# Volterra_Doughter_Board_MKS_GEN_L_2_1.net
KiCad netlist of a schematic drawn in EAGLE
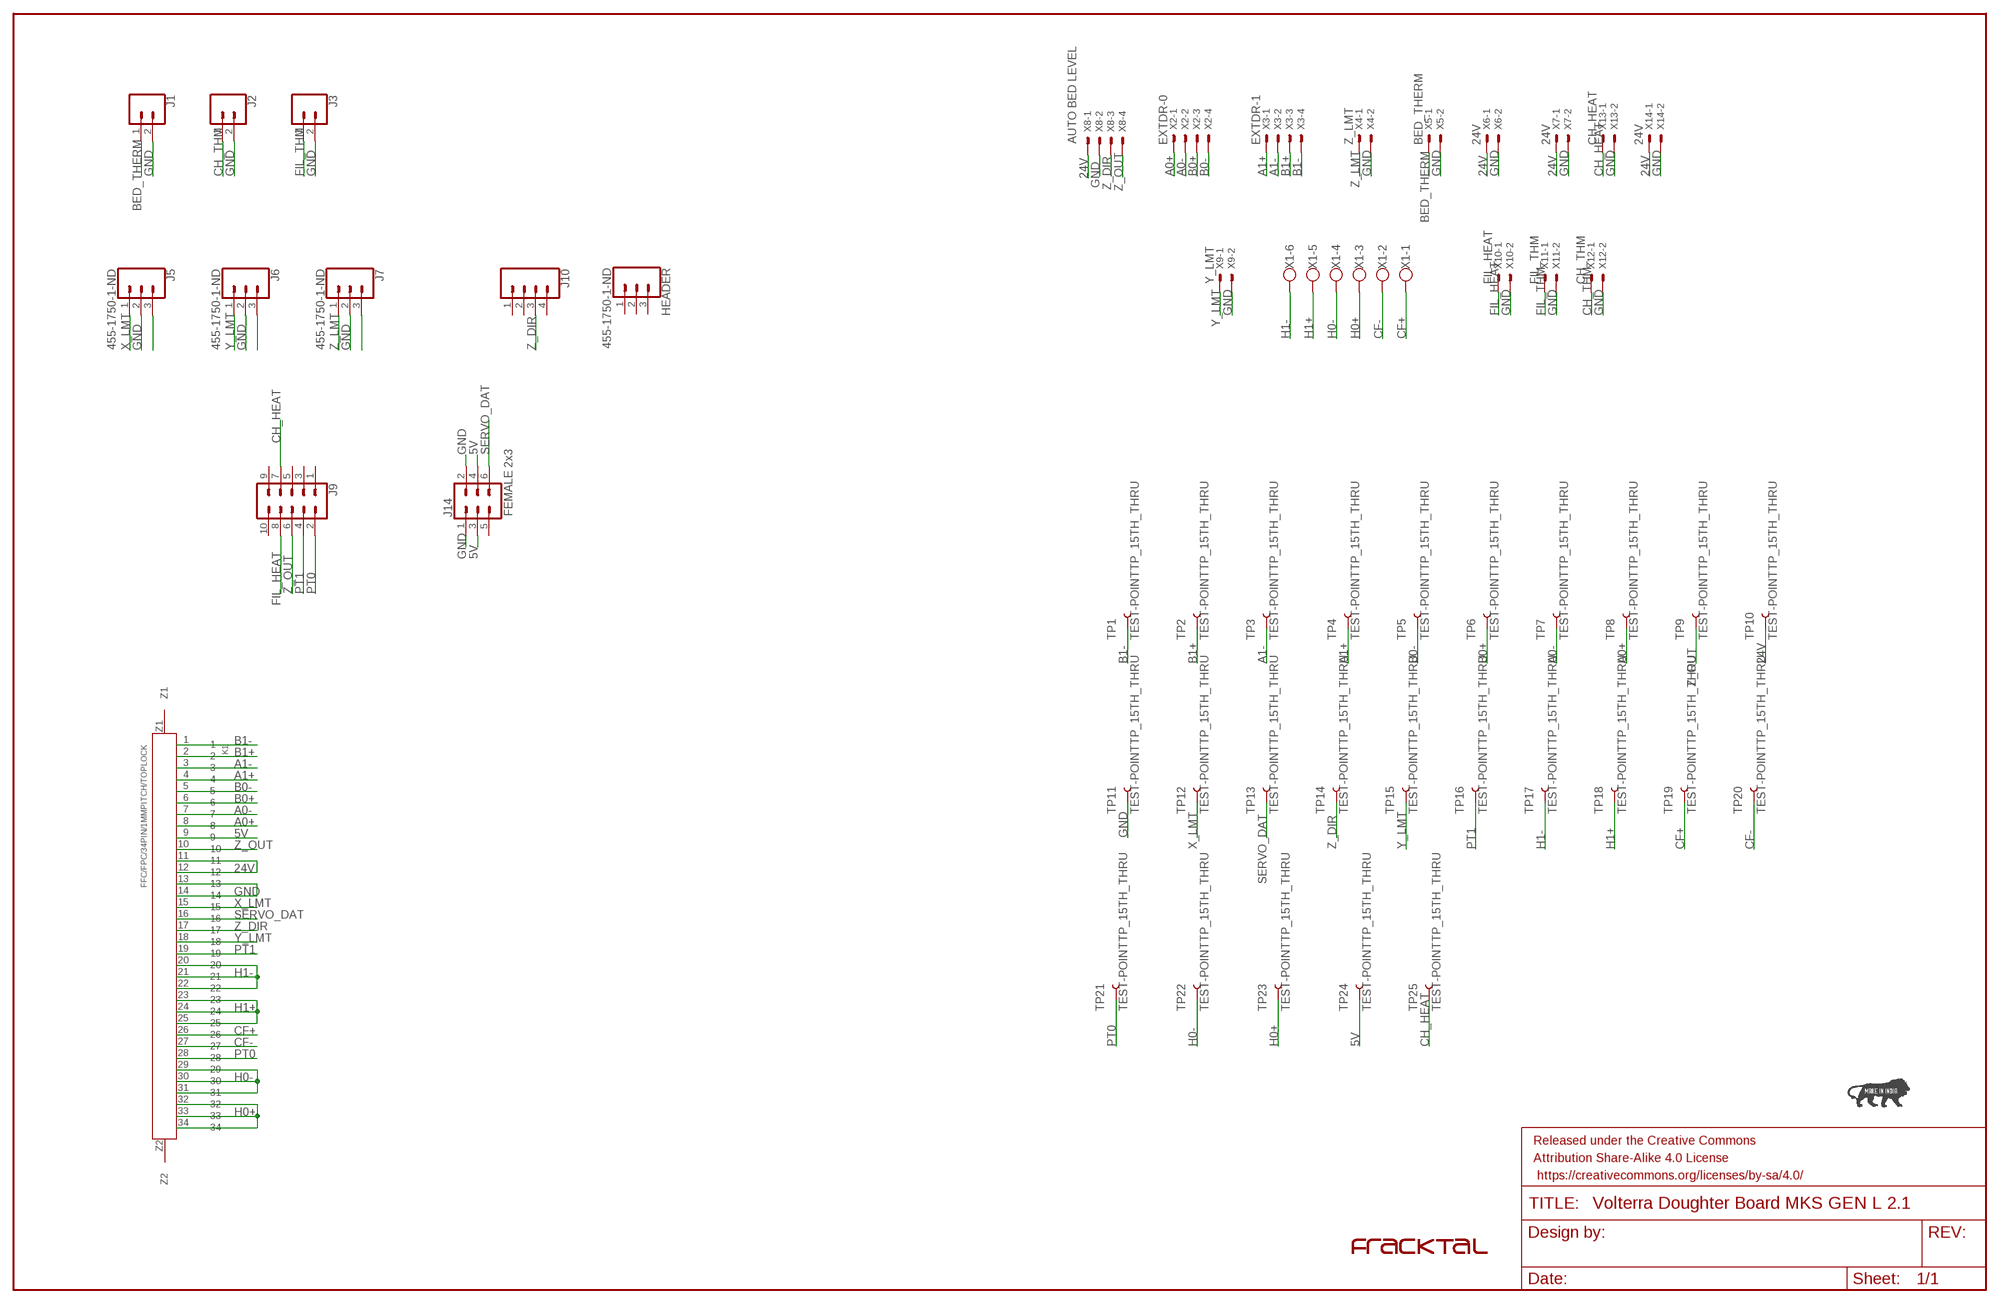
[diagram p0: schematic, sheet 1]

(export (version "E")
  (design (tool "Eeschema 10.0.6"))
  (components
    (comp (ref "FRAME1")
      (value "FRAME-LEDGER")
      (footprint "eagle-import:CREATIVE_COMMONS")
      (libsource (lib "eagle-import") (part "FRAME-LEDGER"))
    )
    (comp (ref "HEADER")
      (value "455-1750-1-ND")
      (footprint "eagle-import:1X03")
      (libsource (lib "eagle-import") (part "CONN_03"))
    )
    (comp (ref "J1")
      (value "CONN_02")
      (footprint "eagle-import:1X02")
      (libsource (lib "eagle-import") (part "CONN_02"))
    )
    (comp (ref "J2")
      (value "CONN_02")
      (footprint "eagle-import:1X02")
      (libsource (lib "eagle-import") (part "CONN_02"))
    )
    (comp (ref "J3")
      (value "CONN_02")
      (footprint "eagle-import:1X02")
      (libsource (lib "eagle-import") (part "CONN_02"))
    )
    (comp (ref "J5")
      (value "455-1750-1-ND")
      (footprint "eagle-import:1X03")
      (libsource (lib "eagle-import") (part "CONN_03"))
    )
    (comp (ref "J6")
      (value "455-1750-1-ND")
      (footprint "eagle-import:1X03")
      (libsource (lib "eagle-import") (part "CONN_03"))
    )
    (comp (ref "J7")
      (value "455-1750-1-ND")
      (footprint "eagle-import:1X03")
      (libsource (lib "eagle-import") (part "CONN_03"))
    )
    (comp (ref "J9")
      (value "CONN_05X2PTH")
      (footprint "eagle-import:2X5")
      (libsource (lib "eagle-import") (part "CONN_05X2PTH"))
    )
    (comp (ref "J10")
      (value "CONN_04")
      (footprint "eagle-import:1X04")
      (libsource (lib "eagle-import") (part "CONN_04"))
    )
    (comp (ref "J14")
      (value "FEMALE 2x3")
      (footprint "eagle-import:2X3")
      (libsource (lib "eagle-import") (part "CONN_03X2FEMALE"))
    )
    (comp (ref "K1")
      (value "FFC/FPC/34PIN/1MMPITCH/TOPLOCK")
      (footprint "eagle-import:34PIN_1MMPITCH_FFC_FPC")
      (libsource (lib "eagle-import") (part "FFC/FPC/34PIN/1MMPITCH/TOPLOCK"))
    )
    (comp (ref "TP1")
      (value "TEST-POINTTP_15TH_THRU")
      (footprint "eagle-import:TP_15TH")
      (libsource (lib "eagle-import") (part "TEST-POINTTP_15TH_THRU"))
    )
    (comp (ref "TP2")
      (value "TEST-POINTTP_15TH_THRU")
      (footprint "eagle-import:TP_15TH")
      (libsource (lib "eagle-import") (part "TEST-POINTTP_15TH_THRU"))
    )
    (comp (ref "TP3")
      (value "TEST-POINTTP_15TH_THRU")
      (footprint "eagle-import:TP_15TH")
      (libsource (lib "eagle-import") (part "TEST-POINTTP_15TH_THRU"))
    )
    (comp (ref "TP4")
      (value "TEST-POINTTP_15TH_THRU")
      (footprint "eagle-import:TP_15TH")
      (libsource (lib "eagle-import") (part "TEST-POINTTP_15TH_THRU"))
    )
    (comp (ref "TP5")
      (value "TEST-POINTTP_15TH_THRU")
      (footprint "eagle-import:TP_15TH")
      (libsource (lib "eagle-import") (part "TEST-POINTTP_15TH_THRU"))
    )
    (comp (ref "TP6")
      (value "TEST-POINTTP_15TH_THRU")
      (footprint "eagle-import:TP_15TH")
      (libsource (lib "eagle-import") (part "TEST-POINTTP_15TH_THRU"))
    )
    (comp (ref "TP7")
      (value "TEST-POINTTP_15TH_THRU")
      (footprint "eagle-import:TP_15TH")
      (libsource (lib "eagle-import") (part "TEST-POINTTP_15TH_THRU"))
    )
    (comp (ref "TP8")
      (value "TEST-POINTTP_15TH_THRU")
      (footprint "eagle-import:TP_15TH")
      (libsource (lib "eagle-import") (part "TEST-POINTTP_15TH_THRU"))
    )
    (comp (ref "TP9")
      (value "TEST-POINTTP_15TH_THRU")
      (footprint "eagle-import:TP_15TH")
      (libsource (lib "eagle-import") (part "TEST-POINTTP_15TH_THRU"))
    )
    (comp (ref "TP10")
      (value "TEST-POINTTP_15TH_THRU")
      (footprint "eagle-import:TP_15TH")
      (libsource (lib "eagle-import") (part "TEST-POINTTP_15TH_THRU"))
    )
    (comp (ref "TP11")
      (value "TEST-POINTTP_15TH_THRU")
      (footprint "eagle-import:TP_15TH")
      (libsource (lib "eagle-import") (part "TEST-POINTTP_15TH_THRU"))
    )
    (comp (ref "TP12")
      (value "TEST-POINTTP_15TH_THRU")
      (footprint "eagle-import:TP_15TH")
      (libsource (lib "eagle-import") (part "TEST-POINTTP_15TH_THRU"))
    )
    (comp (ref "TP13")
      (value "TEST-POINTTP_15TH_THRU")
      (footprint "eagle-import:TP_15TH")
      (libsource (lib "eagle-import") (part "TEST-POINTTP_15TH_THRU"))
    )
    (comp (ref "TP14")
      (value "TEST-POINTTP_15TH_THRU")
      (footprint "eagle-import:TP_15TH")
      (libsource (lib "eagle-import") (part "TEST-POINTTP_15TH_THRU"))
    )
    (comp (ref "TP15")
      (value "TEST-POINTTP_15TH_THRU")
      (footprint "eagle-import:TP_15TH")
      (libsource (lib "eagle-import") (part "TEST-POINTTP_15TH_THRU"))
    )
    (comp (ref "TP16")
      (value "TEST-POINTTP_15TH_THRU")
      (footprint "eagle-import:TP_15TH")
      (libsource (lib "eagle-import") (part "TEST-POINTTP_15TH_THRU"))
    )
    (comp (ref "TP17")
      (value "TEST-POINTTP_15TH_THRU")
      (footprint "eagle-import:TP_15TH")
      (libsource (lib "eagle-import") (part "TEST-POINTTP_15TH_THRU"))
    )
    (comp (ref "TP18")
      (value "TEST-POINTTP_15TH_THRU")
      (footprint "eagle-import:TP_15TH")
      (libsource (lib "eagle-import") (part "TEST-POINTTP_15TH_THRU"))
    )
    (comp (ref "TP19")
      (value "TEST-POINTTP_15TH_THRU")
      (footprint "eagle-import:TP_15TH")
      (libsource (lib "eagle-import") (part "TEST-POINTTP_15TH_THRU"))
    )
    (comp (ref "TP20")
      (value "TEST-POINTTP_15TH_THRU")
      (footprint "eagle-import:TP_15TH")
      (libsource (lib "eagle-import") (part "TEST-POINTTP_15TH_THRU"))
    )
    (comp (ref "TP21")
      (value "TEST-POINTTP_15TH_THRU")
      (footprint "eagle-import:TP_15TH")
      (libsource (lib "eagle-import") (part "TEST-POINTTP_15TH_THRU"))
    )
    (comp (ref "TP22")
      (value "TEST-POINTTP_15TH_THRU")
      (footprint "eagle-import:TP_15TH")
      (libsource (lib "eagle-import") (part "TEST-POINTTP_15TH_THRU"))
    )
    (comp (ref "TP23")
      (value "TEST-POINTTP_15TH_THRU")
      (footprint "eagle-import:TP_15TH")
      (libsource (lib "eagle-import") (part "TEST-POINTTP_15TH_THRU"))
    )
    (comp (ref "TP24")
      (value "TEST-POINTTP_15TH_THRU")
      (footprint "eagle-import:TP_15TH")
      (libsource (lib "eagle-import") (part "TEST-POINTTP_15TH_THRU"))
    )
    (comp (ref "TP25")
      (value "TEST-POINTTP_15TH_THRU")
      (footprint "eagle-import:TP_15TH")
      (libsource (lib "eagle-import") (part "TEST-POINTTP_15TH_THRU"))
    )
    (comp (ref "U$1")
      (value "FRACKTALLOGO")
      (footprint "eagle-import:FRACKTALLOGO")
      (libsource (lib "eagle-import") (part "FRACKTALLOGO"))
    )
    (comp (ref "U$2")
      (value "MAKEININDIA")
      (footprint "eagle-import:MAKEININDIA")
      (libsource (lib "eagle-import") (part "MAKEININDIA"))
    )
    (comp (ref "X1")
      (value "W237-6")
      (footprint "eagle-import:W237-6")
      (libsource (lib "eagle-import") (part "W237-6"))
    )
    (comp (ref "X2")
      (value "EXTDR-0")
      (footprint "eagle-import:JST-XH-04-PACKAGE-LONG-PAD")
      (libsource (lib "eagle-import") (part "JST-XH-04-PIN-LONG-PAD"))
    )
    (comp (ref "X3")
      (value "EXTDR-1")
      (footprint "eagle-import:JST-XH-04-PACKAGE-LONG-PAD")
      (libsource (lib "eagle-import") (part "JST-XH-04-PIN-LONG-PAD"))
    )
    (comp (ref "X4")
      (value "Z_LMT")
      (footprint "eagle-import:JST-XH-02-PACKAGE-LONG-PAD")
      (libsource (lib "eagle-import") (part "JST-XH-02-PIN-LONG-PAD"))
    )
    (comp (ref "X5")
      (value "BED_THERM")
      (footprint "eagle-import:JST-XH-02-PACKAGE-LONG-PAD")
      (libsource (lib "eagle-import") (part "JST-XH-02-PIN-LONG-PAD"))
    )
    (comp (ref "X6")
      (value "24V")
      (footprint "eagle-import:JST-XH-02-PACKAGE-LONG-PAD")
      (libsource (lib "eagle-import") (part "JST-XH-02-PIN-LONG-PAD"))
    )
    (comp (ref "X7")
      (value "24V")
      (footprint "eagle-import:JST-XH-02-PACKAGE-LONG-PAD")
      (libsource (lib "eagle-import") (part "JST-XH-02-PIN-LONG-PAD"))
    )
    (comp (ref "X8")
      (value "AUTO BED LEVELING")
      (footprint "eagle-import:JST-XH-04-PACKAGE-LONG-PAD")
      (fields (field (name "AUTOBEDLEVL") "AUTO BED LEVEL"))
      (libsource (lib "eagle-import") (part "JST-XH-04-PIN-LONG-PAD"))
    )
    (comp (ref "X9")
      (value "Y_LMT")
      (footprint "eagle-import:JST-XH-02-PACKAGE-LONG-PAD")
      (libsource (lib "eagle-import") (part "JST-XH-02-PIN-LONG-PAD"))
    )
    (comp (ref "X10")
      (value "FIL_HEAT")
      (footprint "eagle-import:JST-XH-02-PACKAGE-LONG-PAD")
      (libsource (lib "eagle-import") (part "JST-XH-02-PIN-LONG-PAD"))
    )
    (comp (ref "X11")
      (value "FIL_THM")
      (footprint "eagle-import:JST-XH-02-PACKAGE-LONG-PAD")
      (libsource (lib "eagle-import") (part "JST-XH-02-PIN-LONG-PAD"))
    )
    (comp (ref "X12")
      (value "CH_THM")
      (footprint "eagle-import:JST-XH-02-PACKAGE-LONG-PAD")
      (libsource (lib "eagle-import") (part "JST-XH-02-PIN-LONG-PAD"))
    )
    (comp (ref "X13")
      (value "CH_HEAT")
      (footprint "eagle-import:JST-XH-02-PACKAGE-LONG-PAD")
      (libsource (lib "eagle-import") (part "JST-XH-02-PIN-LONG-PAD"))
    )
    (comp (ref "X14")
      (value "24V")
      (footprint "eagle-import:JST-XH-02-PACKAGE-LONG-PAD")
      (libsource (lib "eagle-import") (part "JST-XH-02-PIN-LONG-PAD"))
    )
  )
  (nets
    (net (code "1") (name "/5V") (class "Default")
      (node (ref "J14") (pin "3") (pinfunction "3_3") (pintype "bidirectional"))
      (node (ref "J14") (pin "4") (pinfunction "4_4") (pintype "bidirectional"))
      (node (ref "K1") (pin "9") (pinfunction "9_9") (pintype "bidirectional"))
      (node (ref "TP24") (pin "P$1") (pinfunction "1_P$1") (pintype "bidirectional"))
    )
    (net (code "2") (name "/24V") (class "Default")
      (node (ref "K1") (pin "11") (pinfunction "11_11") (pintype "bidirectional"))
      (node (ref "K1") (pin "12") (pinfunction "12_12") (pintype "bidirectional"))
      (node (ref "TP10") (pin "P$1") (pinfunction "1_P$1") (pintype "bidirectional"))
      (node (ref "X14") (pin "1") (pinfunction "S_1") (pintype "passive"))
      (node (ref "X6") (pin "1") (pinfunction "S_1") (pintype "passive"))
      (node (ref "X7") (pin "1") (pinfunction "S_1") (pintype "passive"))
      (node (ref "X8") (pin "1") (pinfunction "S_1") (pintype "passive"))
    )
    (net (code "3") (name "/A0+") (class "Default")
      (node (ref "K1") (pin "8") (pinfunction "8_8") (pintype "bidirectional"))
      (node (ref "TP8") (pin "P$1") (pinfunction "1_P$1") (pintype "bidirectional"))
      (node (ref "X2") (pin "1") (pinfunction "S_1") (pintype "passive"))
    )
    (net (code "4") (name "/A0-") (class "Default")
      (node (ref "K1") (pin "7") (pinfunction "7_7") (pintype "bidirectional"))
      (node (ref "TP7") (pin "P$1") (pinfunction "1_P$1") (pintype "bidirectional"))
      (node (ref "X2") (pin "2") (pinfunction "S_2") (pintype "passive"))
    )
    (net (code "5") (name "/A1+") (class "Default")
      (node (ref "K1") (pin "4") (pinfunction "4_4") (pintype "bidirectional"))
      (node (ref "TP4") (pin "P$1") (pinfunction "1_P$1") (pintype "bidirectional"))
      (node (ref "X3") (pin "1") (pinfunction "S_1") (pintype "passive"))
    )
    (net (code "6") (name "/A1-") (class "Default")
      (node (ref "K1") (pin "3") (pinfunction "3_3") (pintype "bidirectional"))
      (node (ref "TP3") (pin "P$1") (pinfunction "1_P$1") (pintype "bidirectional"))
      (node (ref "X3") (pin "2") (pinfunction "S_2") (pintype "passive"))
    )
    (net (code "7") (name "/B0+") (class "Default")
      (node (ref "K1") (pin "6") (pinfunction "6_6") (pintype "bidirectional"))
      (node (ref "TP6") (pin "P$1") (pinfunction "1_P$1") (pintype "bidirectional"))
      (node (ref "X2") (pin "3") (pinfunction "S_3") (pintype "passive"))
    )
    (net (code "8") (name "/B0-") (class "Default")
      (node (ref "K1") (pin "5") (pinfunction "5_5") (pintype "bidirectional"))
      (node (ref "TP5") (pin "P$1") (pinfunction "1_P$1") (pintype "bidirectional"))
      (node (ref "X2") (pin "4") (pinfunction "S_4") (pintype "passive"))
    )
    (net (code "9") (name "/B1+") (class "Default")
      (node (ref "K1") (pin "2") (pinfunction "2_2") (pintype "bidirectional"))
      (node (ref "TP2") (pin "P$1") (pinfunction "1_P$1") (pintype "bidirectional"))
      (node (ref "X3") (pin "3") (pinfunction "S_3") (pintype "passive"))
    )
    (net (code "10") (name "/B1-") (class "Default")
      (node (ref "K1") (pin "1") (pinfunction "1_1") (pintype "bidirectional"))
      (node (ref "TP1") (pin "P$1") (pinfunction "1_P$1") (pintype "bidirectional"))
      (node (ref "X3") (pin "4") (pinfunction "S_4") (pintype "passive"))
    )
    (net (code "11") (name "/BED_THERM") (class "Default")
      (node (ref "J1") (pin "1") (pinfunction "1_1") (pintype "passive"))
      (node (ref "X5") (pin "1") (pinfunction "S_1") (pintype "passive"))
    )
    (net (code "12") (name "/CF+") (class "Default")
      (node (ref "K1") (pin "26") (pinfunction "26_26") (pintype "bidirectional"))
      (node (ref "TP19") (pin "P$1") (pinfunction "1_P$1") (pintype "bidirectional"))
      (node (ref "X1") (pin "1") (pinfunction "KL_1") (pintype "passive"))
    )
    (net (code "13") (name "/CF-") (class "Default")
      (node (ref "K1") (pin "27") (pinfunction "27_27") (pintype "bidirectional"))
      (node (ref "TP20") (pin "P$1") (pinfunction "1_P$1") (pintype "bidirectional"))
      (node (ref "X1") (pin "2") (pinfunction "KL_2") (pintype "passive"))
    )
    (net (code "14") (name "/CH_HEAT") (class "Default")
      (node (ref "J9") (pin "7") (pinfunction "7_7") (pintype "passive"))
      (node (ref "TP25") (pin "P$1") (pinfunction "1_P$1") (pintype "bidirectional"))
      (node (ref "X13") (pin "1") (pinfunction "S_1") (pintype "passive"))
    )
    (net (code "15") (name "/CH_THM") (class "Default")
      (node (ref "J2") (pin "1") (pinfunction "1_1") (pintype "passive"))
      (node (ref "X12") (pin "1") (pinfunction "S_1") (pintype "passive"))
    )
    (net (code "16") (name "/FIL_HEAT") (class "Default")
      (node (ref "J9") (pin "8") (pinfunction "8_8") (pintype "passive"))
      (node (ref "X10") (pin "1") (pinfunction "S_1") (pintype "passive"))
    )
    (net (code "17") (name "/FIL_THM") (class "Default")
      (node (ref "J3") (pin "1") (pinfunction "1_1") (pintype "passive"))
      (node (ref "X11") (pin "1") (pinfunction "S_1") (pintype "passive"))
    )
    (net (code "18") (name "/GND") (class "Default")
      (node (ref "J1") (pin "2") (pinfunction "2_2") (pintype "passive"))
      (node (ref "J14") (pin "1") (pinfunction "1_1") (pintype "bidirectional"))
      (node (ref "J14") (pin "2") (pinfunction "2_2") (pintype "bidirectional"))
      (node (ref "J2") (pin "2") (pinfunction "2_2") (pintype "passive"))
      (node (ref "J3") (pin "2") (pinfunction "2_2") (pintype "passive"))
      (node (ref "J5") (pin "2") (pinfunction "2_2") (pintype "passive"))
      (node (ref "J6") (pin "2") (pinfunction "2_2") (pintype "passive"))
      (node (ref "J7") (pin "2") (pinfunction "2_2") (pintype "passive"))
      (node (ref "K1") (pin "13") (pinfunction "13_13") (pintype "bidirectional"))
      (node (ref "K1") (pin "14") (pinfunction "14_14") (pintype "bidirectional"))
      (node (ref "TP11") (pin "P$1") (pinfunction "1_P$1") (pintype "bidirectional"))
      (node (ref "X10") (pin "2") (pinfunction "S_2") (pintype "passive"))
      (node (ref "X11") (pin "2") (pinfunction "S_2") (pintype "passive"))
      (node (ref "X12") (pin "2") (pinfunction "S_2") (pintype "passive"))
      (node (ref "X13") (pin "2") (pinfunction "S_2") (pintype "passive"))
      (node (ref "X14") (pin "2") (pinfunction "S_2") (pintype "passive"))
      (node (ref "X4") (pin "2") (pinfunction "S_2") (pintype "passive"))
      (node (ref "X5") (pin "2") (pinfunction "S_2") (pintype "passive"))
      (node (ref "X6") (pin "2") (pinfunction "S_2") (pintype "passive"))
      (node (ref "X7") (pin "2") (pinfunction "S_2") (pintype "passive"))
      (node (ref "X8") (pin "2") (pinfunction "S_2") (pintype "passive"))
      (node (ref "X9") (pin "2") (pinfunction "S_2") (pintype "passive"))
    )
    (net (code "19") (name "/H0+") (class "Default")
      (node (ref "K1") (pin "32") (pinfunction "32_32") (pintype "bidirectional"))
      (node (ref "K1") (pin "33") (pinfunction "33_33") (pintype "bidirectional"))
      (node (ref "K1") (pin "34") (pinfunction "34_34") (pintype "bidirectional"))
      (node (ref "TP23") (pin "P$1") (pinfunction "1_P$1") (pintype "bidirectional"))
      (node (ref "X1") (pin "3") (pinfunction "KL_3") (pintype "passive"))
    )
    (net (code "20") (name "/H0-") (class "Default")
      (node (ref "K1") (pin "29") (pinfunction "29_29") (pintype "bidirectional"))
      (node (ref "K1") (pin "30") (pinfunction "30_30") (pintype "bidirectional"))
      (node (ref "K1") (pin "31") (pinfunction "31_31") (pintype "bidirectional"))
      (node (ref "TP22") (pin "P$1") (pinfunction "1_P$1") (pintype "bidirectional"))
      (node (ref "X1") (pin "4") (pinfunction "KL_4") (pintype "passive"))
    )
    (net (code "21") (name "/H1+") (class "Default")
      (node (ref "K1") (pin "23") (pinfunction "23_23") (pintype "bidirectional"))
      (node (ref "K1") (pin "24") (pinfunction "24_24") (pintype "bidirectional"))
      (node (ref "K1") (pin "25") (pinfunction "25_25") (pintype "bidirectional"))
      (node (ref "TP18") (pin "P$1") (pinfunction "1_P$1") (pintype "bidirectional"))
      (node (ref "X1") (pin "5") (pinfunction "KL_5") (pintype "passive"))
    )
    (net (code "22") (name "/H1-") (class "Default")
      (node (ref "K1") (pin "20") (pinfunction "20_20") (pintype "bidirectional"))
      (node (ref "K1") (pin "21") (pinfunction "21_21") (pintype "bidirectional"))
      (node (ref "K1") (pin "22") (pinfunction "22_22") (pintype "bidirectional"))
      (node (ref "TP17") (pin "P$1") (pinfunction "1_P$1") (pintype "bidirectional"))
      (node (ref "X1") (pin "6") (pinfunction "KL_6") (pintype "passive"))
    )
    (net (code "23") (name "/PT0") (class "Default")
      (node (ref "J9") (pin "2") (pinfunction "2_2") (pintype "passive"))
      (node (ref "K1") (pin "28") (pinfunction "28_28") (pintype "bidirectional"))
      (node (ref "TP21") (pin "P$1") (pinfunction "1_P$1") (pintype "bidirectional"))
    )
    (net (code "24") (name "/PT1") (class "Default")
      (node (ref "J9") (pin "4") (pinfunction "4_4") (pintype "passive"))
      (node (ref "K1") (pin "19") (pinfunction "19_19") (pintype "bidirectional"))
      (node (ref "TP16") (pin "P$1") (pinfunction "1_P$1") (pintype "bidirectional"))
    )
    (net (code "25") (name "/SERVO_DAT") (class "Default")
      (node (ref "J14") (pin "6") (pinfunction "6_6") (pintype "bidirectional"))
      (node (ref "K1") (pin "16") (pinfunction "16_16") (pintype "bidirectional"))
      (node (ref "TP13") (pin "P$1") (pinfunction "1_P$1") (pintype "bidirectional"))
    )
    (net (code "26") (name "/X_LMT") (class "Default")
      (node (ref "J5") (pin "1") (pinfunction "1_1") (pintype "passive"))
      (node (ref "K1") (pin "15") (pinfunction "15_15") (pintype "bidirectional"))
      (node (ref "TP12") (pin "P$1") (pinfunction "1_P$1") (pintype "bidirectional"))
    )
    (net (code "27") (name "/Y_LMT") (class "Default")
      (node (ref "J6") (pin "1") (pinfunction "1_1") (pintype "passive"))
      (node (ref "K1") (pin "18") (pinfunction "18_18") (pintype "bidirectional"))
      (node (ref "TP15") (pin "P$1") (pinfunction "1_P$1") (pintype "bidirectional"))
      (node (ref "X9") (pin "1") (pinfunction "S_1") (pintype "passive"))
    )
    (net (code "28") (name "/Z_DIR") (class "Default")
      (node (ref "J10") (pin "3") (pinfunction "3_3") (pintype "passive"))
      (node (ref "K1") (pin "17") (pinfunction "17_17") (pintype "bidirectional"))
      (node (ref "TP14") (pin "P$1") (pinfunction "1_P$1") (pintype "bidirectional"))
      (node (ref "X8") (pin "3") (pinfunction "S_3") (pintype "passive"))
    )
    (net (code "29") (name "/Z_LMT") (class "Default")
      (node (ref "J7") (pin "1") (pinfunction "1_1") (pintype "passive"))
      (node (ref "X4") (pin "1") (pinfunction "S_1") (pintype "passive"))
    )
    (net (code "30") (name "/Z_OUT") (class "Default")
      (node (ref "J9") (pin "6") (pinfunction "6_6") (pintype "passive"))
      (node (ref "K1") (pin "10") (pinfunction "10_10") (pintype "bidirectional"))
      (node (ref "TP9") (pin "P$1") (pinfunction "1_P$1") (pintype "bidirectional"))
      (node (ref "X8") (pin "4") (pinfunction "S_4") (pintype "passive"))
    )
    (net (code "31") (name "unconnected-(HEADER-Pad1)") (class "Default")
      (node (ref "HEADER") (pin "1") (pinfunction "1_1") (pintype "passive"))
    )
    (net (code "32") (name "unconnected-(HEADER-Pad2)") (class "Default")
      (node (ref "HEADER") (pin "2") (pinfunction "2_2") (pintype "passive"))
    )
    (net (code "33") (name "unconnected-(HEADER-Pad3)") (class "Default")
      (node (ref "HEADER") (pin "3") (pinfunction "3_3") (pintype "passive"))
    )
    (net (code "34") (name "unconnected-(J5-Pad3)") (class "Default")
      (node (ref "J5") (pin "3") (pinfunction "3_3") (pintype "passive"))
    )
    (net (code "35") (name "unconnected-(J6-Pad3)") (class "Default")
      (node (ref "J6") (pin "3") (pinfunction "3_3") (pintype "passive"))
    )
    (net (code "36") (name "unconnected-(J7-Pad3)") (class "Default")
      (node (ref "J7") (pin "3") (pinfunction "3_3") (pintype "passive"))
    )
    (net (code "37") (name "unconnected-(J9-Pad1)") (class "Default")
      (node (ref "J9") (pin "1") (pinfunction "1_1") (pintype "passive"))
    )
    (net (code "38") (name "unconnected-(J9-Pad3)") (class "Default")
      (node (ref "J9") (pin "3") (pinfunction "3_3") (pintype "passive"))
    )
    (net (code "39") (name "unconnected-(J9-Pad5)") (class "Default")
      (node (ref "J9") (pin "5") (pinfunction "5_5") (pintype "passive"))
    )
    (net (code "40") (name "unconnected-(J9-Pad9)") (class "Default")
      (node (ref "J9") (pin "9") (pinfunction "9_9") (pintype "passive"))
    )
    (net (code "41") (name "unconnected-(J9-Pad10)") (class "Default")
      (node (ref "J9") (pin "10") (pinfunction "10_10") (pintype "passive"))
    )
    (net (code "42") (name "unconnected-(J10-Pad1)") (class "Default")
      (node (ref "J10") (pin "1") (pinfunction "1_1") (pintype "passive"))
    )
    (net (code "43") (name "unconnected-(J10-Pad2)") (class "Default")
      (node (ref "J10") (pin "2") (pinfunction "2_2") (pintype "passive"))
    )
    (net (code "44") (name "unconnected-(J10-Pad4)") (class "Default")
      (node (ref "J10") (pin "4") (pinfunction "4_4") (pintype "passive"))
    )
    (net (code "45") (name "unconnected-(J14-Pad5)") (class "Default")
      (node (ref "J14") (pin "5") (pinfunction "5_5") (pintype "bidirectional"))
    )
    (net (code "46") (name "unconnected-(K1-PadZ1)") (class "Default")
      (node (ref "K1") (pin "Z1") (pinfunction "Z1_Z1") (pintype "bidirectional"))
    )
    (net (code "47") (name "unconnected-(K1-PadZ2)") (class "Default")
      (node (ref "K1") (pin "Z2") (pinfunction "Z2_Z2") (pintype "bidirectional"))
    )
  )
)
